# Power_Input_FET.net
KiCad netlist of a schematic drawn in Altium Designer
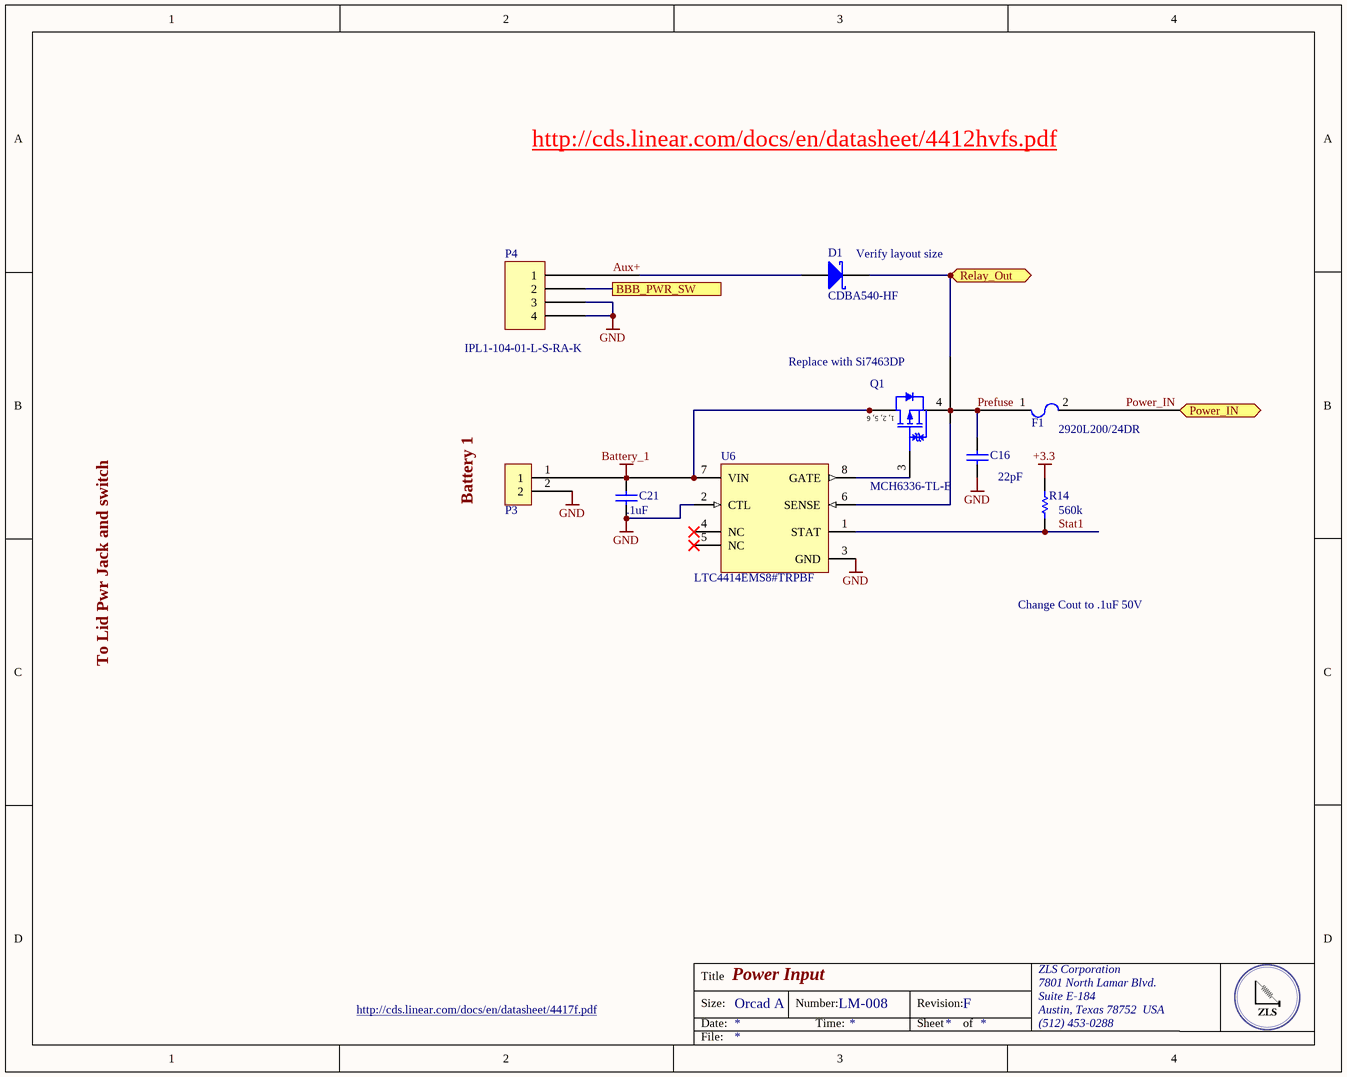
[diagram p0: Power_Input_FET.SchDoc]

(export (version "E")
  (design (tool "Eeschema 10.0.6"))
  (components
    (comp (ref "C16")
      (value "CAP CER 10UF 6.3V X5R 1206")
      (footprint "CAPC1206(3216)130_N")
      (fields
        (field (name "MANUFACTURER") "Taiyo Yuden")
        (field (name "MANUFACTURER PART NUMBER") "JMK316BJ106ML-T")
        (field (name "TOLERANCE") "±20%")
        (field (name "CAPACITANCE") "22pF")
      )
      (libsource (lib "Altium Content Vault") (part "CMP-1037-04913-1"))
    )
    (comp (ref "C21")
      (value "CAP CER 10UF 6.3V X5R 1206")
      (footprint "CAPC1206(3216)130_N")
      (fields
        (field (name "MANUFACTURER") "Taiyo Yuden")
        (field (name "MANUFACTURER PART NUMBER") "JMK316BJ106ML-T")
        (field (name "TOLERANCE") "±20%")
        (field (name "CAPACITANCE") ".1uF")
      )
      (libsource (lib "Altium Content Vault") (part "CMP-1037-04913-1"))
    )
    (comp (ref "D1")
      (value "CDBA540-HF")
      (footprint "VISH-DO-214AC-2_M")
      (description "DIODE SCHOTTKY 40V 5A DO214AB")
      (fields (field (name "MANUFACTURER") "Comchip Technology"))
      (libsource (lib "Miscellaneous Devices") (part "D Schottky"))
    )
    (comp (ref "F1")
      (value "PCT")
      (footprint "CAPC7451X12N")
      (libsource (lib "ZLS_Schematic_lib") (part "PCT"))
    )
    (comp (ref "P3")
      (value "IPL1-102-01-F-S-RA-K")
      (footprint "IPL1-102-01-F-S-RA-K")
      (libsource (lib "ZLS_Schematic_lib") (part "IPL1-102-01-F-S-RA-K"))
    )
    (comp (ref "P4")
      (value "IPL1-104-01-L-S-RA-K")
      (footprint "IPL1-104-01-L-S-RA-K")
      (fields
        (field (name "MANUFACTURER") "Samtec Inc.")
        (field (name "MANUFACTURER PART NUMBER") "IPL1-104-01-L-S-RA-K")
      )
      (libsource (lib "ZLS_Schematic_lib") (part "IPL1-104-01-L-S-RA-K"))
    )
    (comp (ref "Q1")
      (value "MCH6336-TL-E")
      (footprint "ONSC-MCPH-6_V")
      (description "P-Channel Power MOSFET, -12 V, -5 A, 43 mOhm, Single, 6-Pin MCPH, Pb-Free, Tape and Reel")
      (fields (field (name "MANUFACTURER") "On Semiconductor"))
      (libsource (lib "Altium Content Vault") (part "ONSC-PMOS-6_B"))
    )
    (comp (ref "R14")
      (value "560k")
      (footprint "RESC0402(1005)_L")
      (fields (field (name "TOLERANCE") "±1%"))
      (libsource (lib "Altium Content Vault") (part "CMP-1011-00927-1"))
    )
    (comp (ref "U6")
      (value "LTC4414EMS8#TRPBF")
      (footprint "LT-MS8-8_L")
      (fields (field (name "MANUFACTURER") "Linear Technology"))
      (libsource (lib "Altium Content Vault") (part "CMP-0479-00214-1"))
    )
  )
  (nets
    (net (code "1") (name "+3.3") (class "Default")
      (node (ref "R14") (pin "2") (pinfunction "2_2") (pintype "passive"))
    )
    (net (code "2") (name "/Aux+") (class "Default")
      (node (ref "D1") (pin "1") (pinfunction "A_1") (pintype "passive"))
      (node (ref "P4") (pin "1") (pinfunction "1_1") (pintype "passive"))
    )
    (net (code "3") (name "/BBB_PWR_SW") (class "Default")
      (node (ref "P4") (pin "2") (pinfunction "2_2") (pintype "passive"))
    )
    (net (code "4") (name "/Power_IN") (class "Default")
      (node (ref "F1") (pin "2") (pinfunction "2_2") (pintype "passive"))
    )
    (net (code "5") (name "/Prefuse") (class "Default")
      (node (ref "C16") (pin "2") (pinfunction "2_2") (pintype "passive"))
      (node (ref "D1") (pin "2") (pinfunction "K_2") (pintype "passive"))
      (node (ref "F1") (pin "1") (pinfunction "1_1") (pintype "passive"))
      (node (ref "Q1") (pin "4") (pinfunction "S_4") (pintype "passive"))
      (node (ref "U6") (pin "6") (pinfunction "SENSE_6") (pintype "input"))
    )
    (net (code "6") (name "/Stat1") (class "Default")
      (node (ref "R14") (pin "1") (pinfunction "1_1") (pintype "passive"))
      (node (ref "U6") (pin "1") (pinfunction "STAT_1") (pintype "open_collector"))
    )
    (net (code "7") (name "Battery_1") (class "Default")
      (node (ref "C21") (pin "2") (pinfunction "2_2") (pintype "passive"))
      (node (ref "P3") (pin "1") (pinfunction "1_1") (pintype "passive"))
      (node (ref "Q1") (pin "1") (pinfunction "D_1") (pintype "passive"))
      (node (ref "Q1") (pin "2") (pinfunction "D_2") (pintype "passive"))
      (node (ref "Q1") (pin "5") (pinfunction "D_5") (pintype "passive"))
      (node (ref "Q1") (pin "6") (pinfunction "D_6") (pintype "passive"))
      (node (ref "U6") (pin "7") (pinfunction "VIN_7") (pintype "power_in"))
    )
    (net (code "8") (name "GND") (class "Default")
      (node (ref "C16") (pin "1") (pinfunction "1_1") (pintype "passive"))
      (node (ref "C21") (pin "1") (pinfunction "1_1") (pintype "passive"))
      (node (ref "P3") (pin "2") (pinfunction "2_2") (pintype "passive"))
      (node (ref "P4") (pin "3") (pinfunction "3_3") (pintype "passive"))
      (node (ref "P4") (pin "4") (pinfunction "4_4") (pintype "passive"))
      (node (ref "U6") (pin "2") (pinfunction "CTL_2") (pintype "input"))
      (node (ref "U6") (pin "3") (pinfunction "GND_3") (pintype "power_in"))
    )
    (net (code "9") (name "Net-(Q1-G)") (class "Default")
      (node (ref "Q1") (pin "3") (pinfunction "G_3") (pintype "passive"))
      (node (ref "U6") (pin "8") (pinfunction "GATE_8") (pintype "output"))
    )
    (net (code "10") (name "unconnected-(U6-NC-Pad4)") (class "Default")
      (node (ref "U6") (pin "4") (pinfunction "NC_4") (pintype "passive+no_connect"))
    )
    (net (code "11") (name "unconnected-(U6-NC-Pad5)") (class "Default")
      (node (ref "U6") (pin "5") (pinfunction "NC_5") (pintype "passive+no_connect"))
    )
  )
)
